# Oppressor_pcb.net
KiCad netlist of a schematic drawn in EAGLE
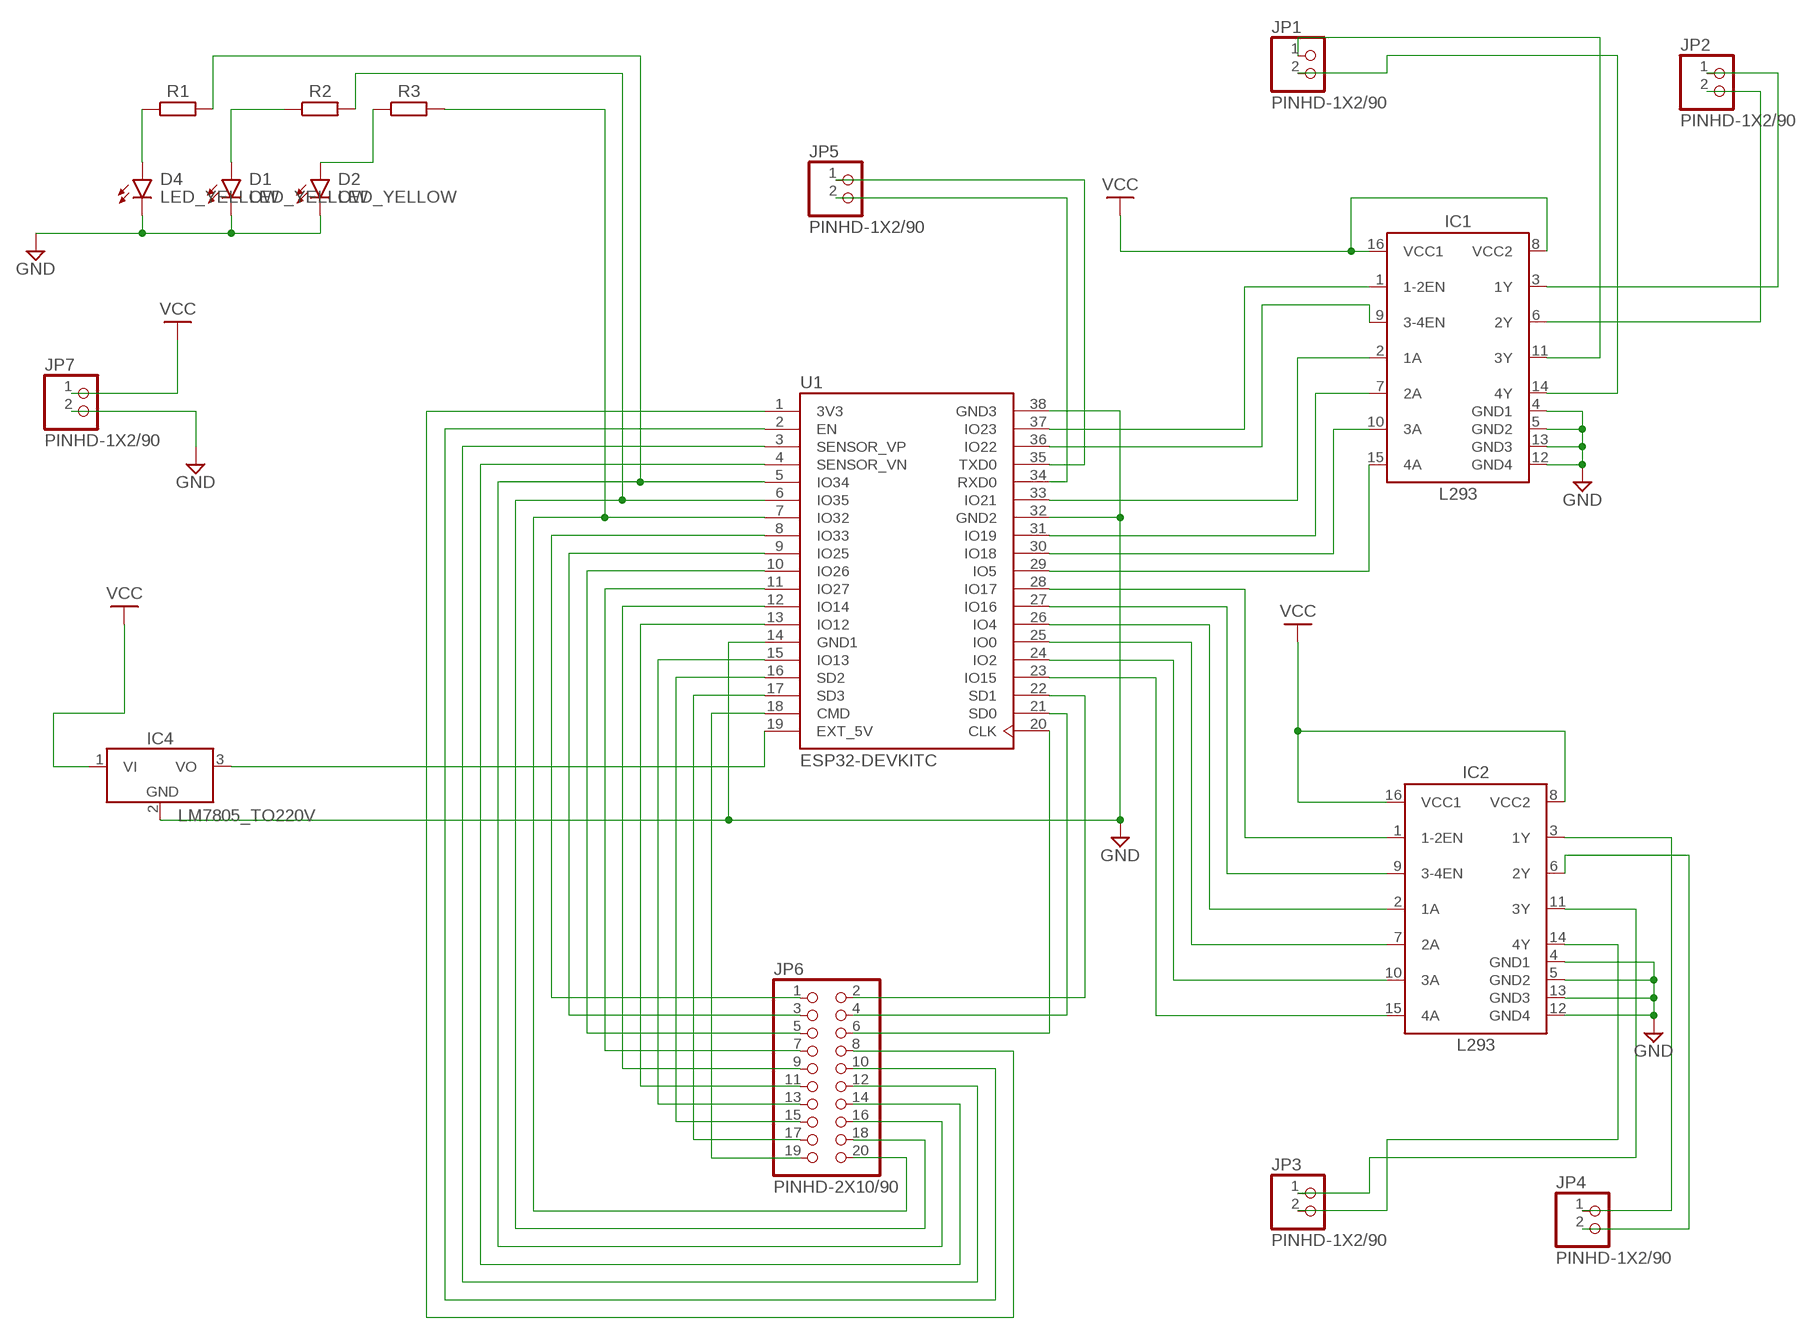
[diagram p0: schematic, sheet 1]

(export (version "E")
  (design (tool "Eeschema 10.0.6"))
  (components
    (comp (ref "D1")
      (value "LED_YELLOW")
      (footprint "eagle-import:LEDC3224X250N_RND-Y")
      (libsource (lib "eagle-import") (part "CHIP-ROUND-Y_1209"))
    )
    (comp (ref "D2")
      (value "LED_YELLOW")
      (footprint "eagle-import:LEDC3224X250N_RND-Y")
      (libsource (lib "eagle-import") (part "CHIP-ROUND-Y_1209"))
    )
    (comp (ref "D4")
      (value "LED_YELLOW")
      (footprint "eagle-import:LEDC3224X250N_RND-Y")
      (libsource (lib "eagle-import") (part "CHIP-ROUND-Y_1209"))
    )
    (comp (ref "IC1")
      (value "L293")
      (footprint "eagle-import:DIP762W53P254L1969H508Q16B")
      (fields (field (name "MANUFACTURER") "Generic"))
      (libsource (lib "eagle-import") (part "L293"))
    )
    (comp (ref "IC2")
      (value "L293")
      (footprint "eagle-import:DIP762W53P254L1969H508Q16B")
      (fields (field (name "MANUFACTURER") "Generic"))
      (libsource (lib "eagle-import") (part "L293"))
    )
    (comp (ref "IC4")
      (value "LM7805_TO220V")
      (footprint "eagle-import:TO220V")
      (fields (field (name "MANUFACTURER") "Generic"))
      (libsource (lib "eagle-import") (part "LM7805_TO220V"))
    )
    (comp (ref "JP1")
      (value "PINHD-1X2/90")
      (footprint "eagle-import:1X02_90")
      (fields (field (name "MANUFACTURER") "Generic"))
      (libsource (lib "eagle-import") (part "PINHD-1X2/90"))
    )
    (comp (ref "JP2")
      (value "PINHD-1X2/90")
      (footprint "eagle-import:1X02_90")
      (fields (field (name "MANUFACTURER") "Generic"))
      (libsource (lib "eagle-import") (part "PINHD-1X2/90"))
    )
    (comp (ref "JP3")
      (value "PINHD-1X2/90")
      (footprint "eagle-import:1X02_90")
      (fields (field (name "MANUFACTURER") "Generic"))
      (libsource (lib "eagle-import") (part "PINHD-1X2/90"))
    )
    (comp (ref "JP4")
      (value "PINHD-1X2/90")
      (footprint "eagle-import:1X02_90")
      (fields (field (name "MANUFACTURER") "Generic"))
      (libsource (lib "eagle-import") (part "PINHD-1X2/90"))
    )
    (comp (ref "JP5")
      (value "PINHD-1X2/90")
      (footprint "eagle-import:1X02_90")
      (fields (field (name "MANUFACTURER") "Generic"))
      (libsource (lib "eagle-import") (part "PINHD-1X2/90"))
    )
    (comp (ref "JP6")
      (value "PINHD-2X10/90")
      (footprint "eagle-import:2X10_90")
      (fields (field (name "MANUFACTURER") "Generic"))
      (libsource (lib "eagle-import") (part "PINHD-2X10/90"))
    )
    (comp (ref "JP7")
      (value "PINHD-1X2/90")
      (footprint "eagle-import:1X02_90")
      (fields (field (name "MANUFACTURER") "Generic"))
      (libsource (lib "eagle-import") (part "PINHD-1X2/90"))
    )
    (comp (ref "R1")
      (value "R_AXIAL-7.2MM-PITCH")
      (footprint "eagle-import:RESAD724W46L381D178B")
      (libsource (lib "eagle-import") (part "RAXIAL-7.2MM-PITCH_"))
    )
    (comp (ref "R2")
      (value "R_AXIAL-7.2MM-PITCH")
      (footprint "eagle-import:RESAD724W46L381D178B")
      (libsource (lib "eagle-import") (part "RAXIAL-7.2MM-PITCH_"))
    )
    (comp (ref "R3")
      (value "R_AXIAL-7.2MM-PITCH")
      (footprint "eagle-import:RESAD724W46L381D178B")
      (libsource (lib "eagle-import") (part "RAXIAL-7.2MM-PITCH_"))
    )
    (comp (ref "U1")
      (value "ESP32-DEVKITC")
      (footprint "eagle-import:MODULE_ESP32-DEVKITC")
      (fields (field (name "MANUFACTURER") "ESPRESSIF"))
      (libsource (lib "eagle-import") (part "ESP32-DEVKITC"))
    )
  )
  (nets
    (net (code "1") (name "GND") (class "Default")
      (node (ref "D1") (pin "C") (pinfunction "C_C") (pintype "passive"))
      (node (ref "D2") (pin "C") (pinfunction "C_C") (pintype "passive"))
      (node (ref "D4") (pin "C") (pinfunction "C_C") (pintype "passive"))
      (node (ref "IC1") (pin "12") (pinfunction "GND4_12") (pintype "passive"))
      (node (ref "IC1") (pin "13") (pinfunction "GND3_13") (pintype "passive"))
      (node (ref "IC1") (pin "4") (pinfunction "GND1_4") (pintype "passive"))
      (node (ref "IC1") (pin "5") (pinfunction "GND2_5") (pintype "passive"))
      (node (ref "IC2") (pin "12") (pinfunction "GND4_12") (pintype "passive"))
      (node (ref "IC2") (pin "13") (pinfunction "GND3_13") (pintype "passive"))
      (node (ref "IC2") (pin "4") (pinfunction "GND1_4") (pintype "passive"))
      (node (ref "IC2") (pin "5") (pinfunction "GND2_5") (pintype "passive"))
      (node (ref "IC4") (pin "2") (pinfunction "GND_2") (pintype "passive"))
      (node (ref "JP7") (pin "2") (pinfunction "2_2") (pintype "passive"))
      (node (ref "U1") (pin "14") (pinfunction "GND1_14") (pintype "power_in"))
      (node (ref "U1") (pin "32") (pinfunction "GND2_32") (pintype "power_in"))
      (node (ref "U1") (pin "38") (pinfunction "GND3_38") (pintype "power_in"))
    )
    (net (code "2") (name "Net-(D1-PadA)") (class "Default")
      (node (ref "D1") (pin "A") (pinfunction "A_A") (pintype "passive"))
      (node (ref "R2") (pin "1") (pinfunction "1_1") (pintype "passive"))
    )
    (net (code "3") (name "Net-(D2-PadA)") (class "Default")
      (node (ref "D2") (pin "A") (pinfunction "A_A") (pintype "passive"))
      (node (ref "R3") (pin "1") (pinfunction "1_1") (pintype "passive"))
    )
    (net (code "4") (name "Net-(D4-PadA)") (class "Default")
      (node (ref "D4") (pin "A") (pinfunction "A_A") (pintype "passive"))
      (node (ref "R1") (pin "1") (pinfunction "1_1") (pintype "passive"))
    )
    (net (code "5") (name "Net-(IC1-1-2EN)") (class "Default")
      (node (ref "IC1") (pin "1") (pinfunction "1-2EN_1") (pintype "input"))
      (node (ref "U1") (pin "37") (pinfunction "IO23_37") (pintype "bidirectional"))
    )
    (net (code "6") (name "Net-(IC1-1A)") (class "Default")
      (node (ref "IC1") (pin "2") (pinfunction "1A_2") (pintype "input"))
      (node (ref "U1") (pin "33") (pinfunction "IO21_33") (pintype "bidirectional"))
    )
    (net (code "7") (name "Net-(IC1-1Y)") (class "Default")
      (node (ref "IC1") (pin "3") (pinfunction "1Y_3") (pintype "output"))
      (node (ref "JP2") (pin "1") (pinfunction "1_1") (pintype "passive"))
    )
    (net (code "8") (name "Net-(IC1-2A)") (class "Default")
      (node (ref "IC1") (pin "7") (pinfunction "2A_7") (pintype "input"))
      (node (ref "U1") (pin "31") (pinfunction "IO19_31") (pintype "bidirectional"))
    )
    (net (code "9") (name "Net-(IC1-2Y)") (class "Default")
      (node (ref "IC1") (pin "6") (pinfunction "2Y_6") (pintype "output"))
      (node (ref "JP2") (pin "2") (pinfunction "2_2") (pintype "passive"))
    )
    (net (code "10") (name "Net-(IC1-3-4EN)") (class "Default")
      (node (ref "IC1") (pin "9") (pinfunction "3-4EN_9") (pintype "input"))
      (node (ref "U1") (pin "36") (pinfunction "IO22_36") (pintype "bidirectional"))
    )
    (net (code "11") (name "Net-(IC1-3A)") (class "Default")
      (node (ref "IC1") (pin "10") (pinfunction "3A_10") (pintype "input"))
      (node (ref "U1") (pin "30") (pinfunction "IO18_30") (pintype "bidirectional"))
    )
    (net (code "12") (name "Net-(IC1-3Y)") (class "Default")
      (node (ref "IC1") (pin "11") (pinfunction "3Y_11") (pintype "output"))
      (node (ref "JP1") (pin "1") (pinfunction "1_1") (pintype "passive"))
    )
    (net (code "13") (name "Net-(IC1-4A)") (class "Default")
      (node (ref "IC1") (pin "15") (pinfunction "4A_15") (pintype "input"))
      (node (ref "U1") (pin "29") (pinfunction "IO5_29") (pintype "bidirectional"))
    )
    (net (code "14") (name "Net-(IC1-4Y)") (class "Default")
      (node (ref "IC1") (pin "14") (pinfunction "4Y_14") (pintype "output"))
      (node (ref "JP1") (pin "2") (pinfunction "2_2") (pintype "passive"))
    )
    (net (code "15") (name "Net-(IC2-1-2EN)") (class "Default")
      (node (ref "IC2") (pin "1") (pinfunction "1-2EN_1") (pintype "input"))
      (node (ref "U1") (pin "28") (pinfunction "IO17_28") (pintype "bidirectional"))
    )
    (net (code "16") (name "Net-(IC2-1A)") (class "Default")
      (node (ref "IC2") (pin "2") (pinfunction "1A_2") (pintype "input"))
      (node (ref "U1") (pin "26") (pinfunction "IO4_26") (pintype "bidirectional"))
    )
    (net (code "17") (name "Net-(IC2-1Y)") (class "Default")
      (node (ref "IC2") (pin "3") (pinfunction "1Y_3") (pintype "output"))
      (node (ref "JP4") (pin "1") (pinfunction "1_1") (pintype "passive"))
    )
    (net (code "18") (name "Net-(IC2-2A)") (class "Default")
      (node (ref "IC2") (pin "7") (pinfunction "2A_7") (pintype "input"))
      (node (ref "U1") (pin "25") (pinfunction "IO0_25") (pintype "bidirectional"))
    )
    (net (code "19") (name "Net-(IC2-2Y)") (class "Default")
      (node (ref "IC2") (pin "6") (pinfunction "2Y_6") (pintype "output"))
      (node (ref "JP4") (pin "2") (pinfunction "2_2") (pintype "passive"))
    )
    (net (code "20") (name "Net-(IC2-3-4EN)") (class "Default")
      (node (ref "IC2") (pin "9") (pinfunction "3-4EN_9") (pintype "input"))
      (node (ref "U1") (pin "27") (pinfunction "IO16_27") (pintype "bidirectional"))
    )
    (net (code "21") (name "Net-(IC2-3A)") (class "Default")
      (node (ref "IC2") (pin "10") (pinfunction "3A_10") (pintype "input"))
      (node (ref "U1") (pin "24") (pinfunction "IO2_24") (pintype "bidirectional"))
    )
    (net (code "22") (name "Net-(IC2-3Y)") (class "Default")
      (node (ref "IC2") (pin "11") (pinfunction "3Y_11") (pintype "output"))
      (node (ref "JP3") (pin "1") (pinfunction "1_1") (pintype "passive"))
    )
    (net (code "23") (name "Net-(IC2-4A)") (class "Default")
      (node (ref "IC2") (pin "15") (pinfunction "4A_15") (pintype "input"))
      (node (ref "U1") (pin "23") (pinfunction "IO15_23") (pintype "bidirectional"))
    )
    (net (code "24") (name "Net-(IC2-4Y)") (class "Default")
      (node (ref "IC2") (pin "14") (pinfunction "4Y_14") (pintype "output"))
      (node (ref "JP3") (pin "2") (pinfunction "2_2") (pintype "passive"))
    )
    (net (code "25") (name "Net-(IC4-VO)") (class "Default")
      (node (ref "IC4") (pin "3") (pinfunction "VO_3") (pintype "output"))
      (node (ref "U1") (pin "19") (pinfunction "EXT_5V_19") (pintype "power_in"))
    )
    (net (code "26") (name "Net-(U1-3V3)") (class "Default")
      (node (ref "JP6") (pin "8") (pinfunction "8_8") (pintype "passive"))
      (node (ref "U1") (pin "1") (pinfunction "3V3_1") (pintype "power_in"))
    )
    (net (code "27") (name "Net-(U1-CLK)") (class "Default")
      (node (ref "JP6") (pin "6") (pinfunction "6_6") (pintype "passive"))
      (node (ref "U1") (pin "20") (pinfunction "CLK_20") (pintype "input"))
    )
    (net (code "28") (name "Net-(U1-CMD)") (class "Default")
      (node (ref "JP6") (pin "19") (pinfunction "19_19") (pintype "passive"))
      (node (ref "U1") (pin "18") (pinfunction "CMD_18") (pintype "bidirectional"))
    )
    (net (code "29") (name "Net-(U1-EN)") (class "Default")
      (node (ref "JP6") (pin "10") (pinfunction "10_10") (pintype "passive"))
      (node (ref "U1") (pin "2") (pinfunction "EN_2") (pintype "input"))
    )
    (net (code "30") (name "Net-(U1-IO12)") (class "Default")
      (node (ref "JP6") (pin "11") (pinfunction "11_11") (pintype "passive"))
      (node (ref "U1") (pin "13") (pinfunction "IO12_13") (pintype "bidirectional"))
    )
    (net (code "31") (name "Net-(U1-IO13)") (class "Default")
      (node (ref "JP6") (pin "13") (pinfunction "13_13") (pintype "passive"))
      (node (ref "U1") (pin "15") (pinfunction "IO13_15") (pintype "bidirectional"))
    )
    (net (code "32") (name "Net-(U1-IO14)") (class "Default")
      (node (ref "JP6") (pin "9") (pinfunction "9_9") (pintype "passive"))
      (node (ref "U1") (pin "12") (pinfunction "IO14_12") (pintype "bidirectional"))
    )
    (net (code "33") (name "Net-(U1-IO25)") (class "Default")
      (node (ref "JP6") (pin "3") (pinfunction "3_3") (pintype "passive"))
      (node (ref "U1") (pin "9") (pinfunction "IO25_9") (pintype "bidirectional"))
    )
    (net (code "34") (name "Net-(U1-IO26)") (class "Default")
      (node (ref "JP6") (pin "5") (pinfunction "5_5") (pintype "passive"))
      (node (ref "U1") (pin "10") (pinfunction "IO26_10") (pintype "bidirectional"))
    )
    (net (code "35") (name "Net-(U1-IO27)") (class "Default")
      (node (ref "JP6") (pin "7") (pinfunction "7_7") (pintype "passive"))
      (node (ref "U1") (pin "11") (pinfunction "IO27_11") (pintype "bidirectional"))
    )
    (net (code "36") (name "Net-(U1-IO32)") (class "Default")
      (node (ref "JP6") (pin "20") (pinfunction "20_20") (pintype "passive"))
      (node (ref "R3") (pin "2") (pinfunction "2_2") (pintype "passive"))
      (node (ref "U1") (pin "7") (pinfunction "IO32_7") (pintype "bidirectional"))
    )
    (net (code "37") (name "Net-(U1-IO33)") (class "Default")
      (node (ref "JP6") (pin "1") (pinfunction "1_1") (pintype "passive"))
      (node (ref "U1") (pin "8") (pinfunction "IO33_8") (pintype "bidirectional"))
    )
    (net (code "38") (name "Net-(U1-IO34)") (class "Default")
      (node (ref "JP6") (pin "16") (pinfunction "16_16") (pintype "passive"))
      (node (ref "R1") (pin "2") (pinfunction "2_2") (pintype "passive"))
      (node (ref "U1") (pin "5") (pinfunction "IO34_5") (pintype "bidirectional"))
    )
    (net (code "39") (name "Net-(U1-IO35)") (class "Default")
      (node (ref "JP6") (pin "18") (pinfunction "18_18") (pintype "passive"))
      (node (ref "R2") (pin "2") (pinfunction "2_2") (pintype "passive"))
      (node (ref "U1") (pin "6") (pinfunction "IO35_6") (pintype "bidirectional"))
    )
    (net (code "40") (name "Net-(U1-RXD0)") (class "Default")
      (node (ref "JP5") (pin "2") (pinfunction "2_2") (pintype "passive"))
      (node (ref "U1") (pin "34") (pinfunction "RXD0_34") (pintype "input"))
    )
    (net (code "41") (name "Net-(U1-SD0)") (class "Default")
      (node (ref "JP6") (pin "4") (pinfunction "4_4") (pintype "passive"))
      (node (ref "U1") (pin "21") (pinfunction "SD0_21") (pintype "bidirectional"))
    )
    (net (code "42") (name "Net-(U1-SD1)") (class "Default")
      (node (ref "JP6") (pin "2") (pinfunction "2_2") (pintype "passive"))
      (node (ref "U1") (pin "22") (pinfunction "SD1_22") (pintype "bidirectional"))
    )
    (net (code "43") (name "Net-(U1-SD2)") (class "Default")
      (node (ref "JP6") (pin "15") (pinfunction "15_15") (pintype "passive"))
      (node (ref "U1") (pin "16") (pinfunction "SD2_16") (pintype "bidirectional"))
    )
    (net (code "44") (name "Net-(U1-SD3)") (class "Default")
      (node (ref "JP6") (pin "17") (pinfunction "17_17") (pintype "passive"))
      (node (ref "U1") (pin "17") (pinfunction "SD3_17") (pintype "bidirectional"))
    )
    (net (code "45") (name "Net-(U1-SENSOR_VN)") (class "Default")
      (node (ref "JP6") (pin "14") (pinfunction "14_14") (pintype "passive"))
      (node (ref "U1") (pin "4") (pinfunction "SENSOR_VN_4") (pintype "input"))
    )
    (net (code "46") (name "Net-(U1-SENSOR_VP)") (class "Default")
      (node (ref "JP6") (pin "12") (pinfunction "12_12") (pintype "passive"))
      (node (ref "U1") (pin "3") (pinfunction "SENSOR_VP_3") (pintype "input"))
    )
    (net (code "47") (name "Net-(U1-TXD0)") (class "Default")
      (node (ref "JP5") (pin "1") (pinfunction "1_1") (pintype "passive"))
      (node (ref "U1") (pin "35") (pinfunction "TXD0_35") (pintype "output"))
    )
    (net (code "48") (name "VCC") (class "Default")
      (node (ref "IC1") (pin "16") (pinfunction "VCC1_16") (pintype "passive"))
      (node (ref "IC1") (pin "8") (pinfunction "VCC2_8") (pintype "passive"))
      (node (ref "IC2") (pin "16") (pinfunction "VCC1_16") (pintype "passive"))
      (node (ref "IC2") (pin "8") (pinfunction "VCC2_8") (pintype "passive"))
      (node (ref "IC4") (pin "1") (pinfunction "VI_1") (pintype "input"))
      (node (ref "JP7") (pin "1") (pinfunction "1_1") (pintype "passive"))
    )
  )
)
